# MCU.net
KiCad netlist of a schematic drawn in Altium Designer
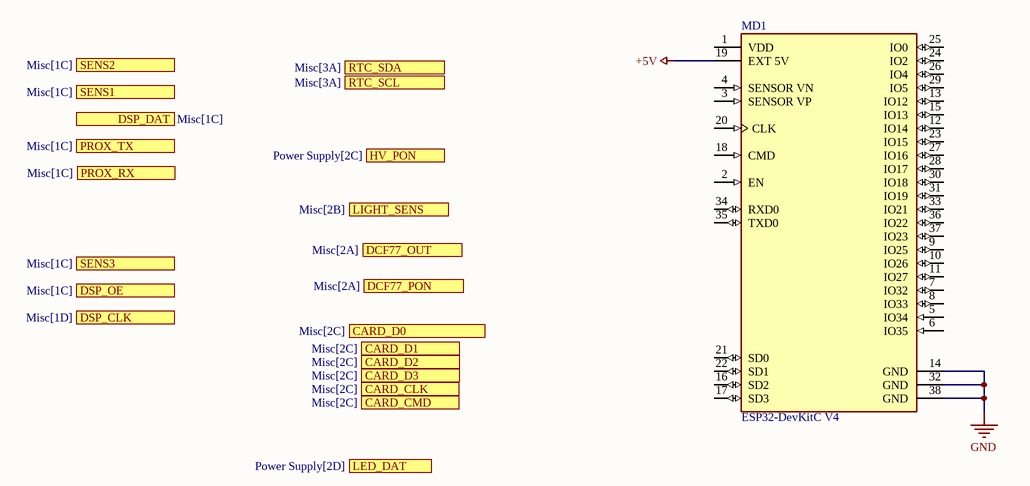
[diagram p0: MCU.SchDoc]

(export (version "E")
  (design (tool "Eeschema 10.0.6"))
  (components
    (comp (ref "MD1")
      (value "ESP32-DevKitC V4")
      (footprint "FP-ESP32-DevKitC_V4-MFG")
      (description "WiFi Development Tools (802.11) ESP32 General Development Kit, ESP32-WROOM-32 on the board")
      (fields
        (field (name "OCTOPART") "https://octopart.com/esp32-devkitc+v4-espressif+systems-107467262")
        (field (name "MANUFACTURER") "Espressif")
      )
      (libsource (lib "Altium Content Vault") (part "5ae961a1152c677524a60dea72d22f3"))
    )
  )
  (nets
    (net (code "1") (name "+5V") (class "Default")
      (node (ref "MD1") (pin "19") (pinfunction "EXT_5V_19") (pintype "power_in"))
    )
    (net (code "23") (name "GND") (class "Default")
      (node (ref "MD1") (pin "14") (pinfunction "GND_14") (pintype "power_in"))
      (node (ref "MD1") (pin "32") (pinfunction "GND_32") (pintype "power_in"))
      (node (ref "MD1") (pin "38") (pinfunction "GND_38") (pintype "power_in"))
    )
    (net (code "24") (name "unconnected-(MD1-CLK-Pad20)") (class "Default")
      (node (ref "MD1") (pin "20") (pinfunction "CLK_20") (pintype "input"))
    )
    (net (code "25") (name "unconnected-(MD1-CMD-Pad18)") (class "Default")
      (node (ref "MD1") (pin "18") (pinfunction "CMD_18") (pintype "input"))
    )
    (net (code "26") (name "unconnected-(MD1-EN-Pad2)") (class "Default")
      (node (ref "MD1") (pin "2") (pinfunction "EN_2") (pintype "input"))
    )
    (net (code "27") (name "unconnected-(MD1-IO0-Pad25)") (class "Default")
      (node (ref "MD1") (pin "25") (pinfunction "IO0_25") (pintype "bidirectional"))
    )
    (net (code "28") (name "unconnected-(MD1-IO2-Pad24)") (class "Default")
      (node (ref "MD1") (pin "24") (pinfunction "IO2_24") (pintype "bidirectional"))
    )
    (net (code "29") (name "unconnected-(MD1-IO4-Pad26)") (class "Default")
      (node (ref "MD1") (pin "26") (pinfunction "IO4_26") (pintype "bidirectional"))
    )
    (net (code "30") (name "unconnected-(MD1-IO5-Pad29)") (class "Default")
      (node (ref "MD1") (pin "29") (pinfunction "IO5_29") (pintype "bidirectional"))
    )
    (net (code "31") (name "unconnected-(MD1-IO12-Pad13)") (class "Default")
      (node (ref "MD1") (pin "13") (pinfunction "IO12_13") (pintype "bidirectional"))
    )
    (net (code "32") (name "unconnected-(MD1-IO13-Pad15)") (class "Default")
      (node (ref "MD1") (pin "15") (pinfunction "IO13_15") (pintype "bidirectional"))
    )
    (net (code "33") (name "unconnected-(MD1-IO14-Pad12)") (class "Default")
      (node (ref "MD1") (pin "12") (pinfunction "IO14_12") (pintype "bidirectional"))
    )
    (net (code "34") (name "unconnected-(MD1-IO15-Pad23)") (class "Default")
      (node (ref "MD1") (pin "23") (pinfunction "IO15_23") (pintype "bidirectional"))
    )
    (net (code "35") (name "unconnected-(MD1-IO16-Pad27)") (class "Default")
      (node (ref "MD1") (pin "27") (pinfunction "IO16_27") (pintype "bidirectional"))
    )
    (net (code "36") (name "unconnected-(MD1-IO17-Pad28)") (class "Default")
      (node (ref "MD1") (pin "28") (pinfunction "IO17_28") (pintype "bidirectional"))
    )
    (net (code "37") (name "unconnected-(MD1-IO18-Pad30)") (class "Default")
      (node (ref "MD1") (pin "30") (pinfunction "IO18_30") (pintype "bidirectional"))
    )
    (net (code "38") (name "unconnected-(MD1-IO19-Pad31)") (class "Default")
      (node (ref "MD1") (pin "31") (pinfunction "IO19_31") (pintype "bidirectional"))
    )
    (net (code "39") (name "unconnected-(MD1-IO21-Pad33)") (class "Default")
      (node (ref "MD1") (pin "33") (pinfunction "IO21_33") (pintype "bidirectional"))
    )
    (net (code "40") (name "unconnected-(MD1-IO22-Pad36)") (class "Default")
      (node (ref "MD1") (pin "36") (pinfunction "IO22_36") (pintype "bidirectional"))
    )
    (net (code "41") (name "unconnected-(MD1-IO23-Pad37)") (class "Default")
      (node (ref "MD1") (pin "37") (pinfunction "IO23_37") (pintype "bidirectional"))
    )
    (net (code "42") (name "unconnected-(MD1-IO25-Pad9)") (class "Default")
      (node (ref "MD1") (pin "9") (pinfunction "IO25_9") (pintype "bidirectional"))
    )
    (net (code "43") (name "unconnected-(MD1-IO26-Pad10)") (class "Default")
      (node (ref "MD1") (pin "10") (pinfunction "IO26_10") (pintype "bidirectional"))
    )
    (net (code "44") (name "unconnected-(MD1-IO27-Pad11)") (class "Default")
      (node (ref "MD1") (pin "11") (pinfunction "IO27_11") (pintype "bidirectional"))
    )
    (net (code "45") (name "unconnected-(MD1-IO32-Pad7)") (class "Default")
      (node (ref "MD1") (pin "7") (pinfunction "IO32_7") (pintype "bidirectional"))
    )
    (net (code "46") (name "unconnected-(MD1-IO33-Pad8)") (class "Default")
      (node (ref "MD1") (pin "8") (pinfunction "IO33_8") (pintype "bidirectional"))
    )
    (net (code "47") (name "unconnected-(MD1-IO34-Pad5)") (class "Default")
      (node (ref "MD1") (pin "5") (pinfunction "IO34_5") (pintype "input"))
    )
    (net (code "48") (name "unconnected-(MD1-IO35-Pad6)") (class "Default")
      (node (ref "MD1") (pin "6") (pinfunction "IO35_6") (pintype "input"))
    )
    (net (code "49") (name "unconnected-(MD1-RXD0-Pad34)") (class "Default")
      (node (ref "MD1") (pin "34") (pinfunction "RXD0_34") (pintype "bidirectional"))
    )
    (net (code "50") (name "unconnected-(MD1-SD0-Pad21)") (class "Default")
      (node (ref "MD1") (pin "21") (pinfunction "SD0_21") (pintype "bidirectional"))
    )
    (net (code "51") (name "unconnected-(MD1-SD1-Pad22)") (class "Default")
      (node (ref "MD1") (pin "22") (pinfunction "SD1_22") (pintype "bidirectional"))
    )
    (net (code "52") (name "unconnected-(MD1-SD2-Pad16)") (class "Default")
      (node (ref "MD1") (pin "16") (pinfunction "SD2_16") (pintype "bidirectional"))
    )
    (net (code "53") (name "unconnected-(MD1-SD3-Pad17)") (class "Default")
      (node (ref "MD1") (pin "17") (pinfunction "SD3_17") (pintype "bidirectional"))
    )
    (net (code "54") (name "unconnected-(MD1-SENSOR_VN-Pad4)") (class "Default")
      (node (ref "MD1") (pin "4") (pinfunction "SENSOR_VN_4") (pintype "input"))
    )
    (net (code "55") (name "unconnected-(MD1-SENSOR_VP-Pad3)") (class "Default")
      (node (ref "MD1") (pin "3") (pinfunction "SENSOR_VP_3") (pintype "input"))
    )
    (net (code "56") (name "unconnected-(MD1-TXD0-Pad35)") (class "Default")
      (node (ref "MD1") (pin "35") (pinfunction "TXD0_35") (pintype "bidirectional"))
    )
    (net (code "57") (name "unconnected-(MD1-VDD-Pad1)") (class "Default")
      (node (ref "MD1") (pin "1") (pinfunction "VDD_1") (pintype "power_in"))
    )
  )
)
